# SD.net
KiCad netlist of a schematic drawn in Altium Designer
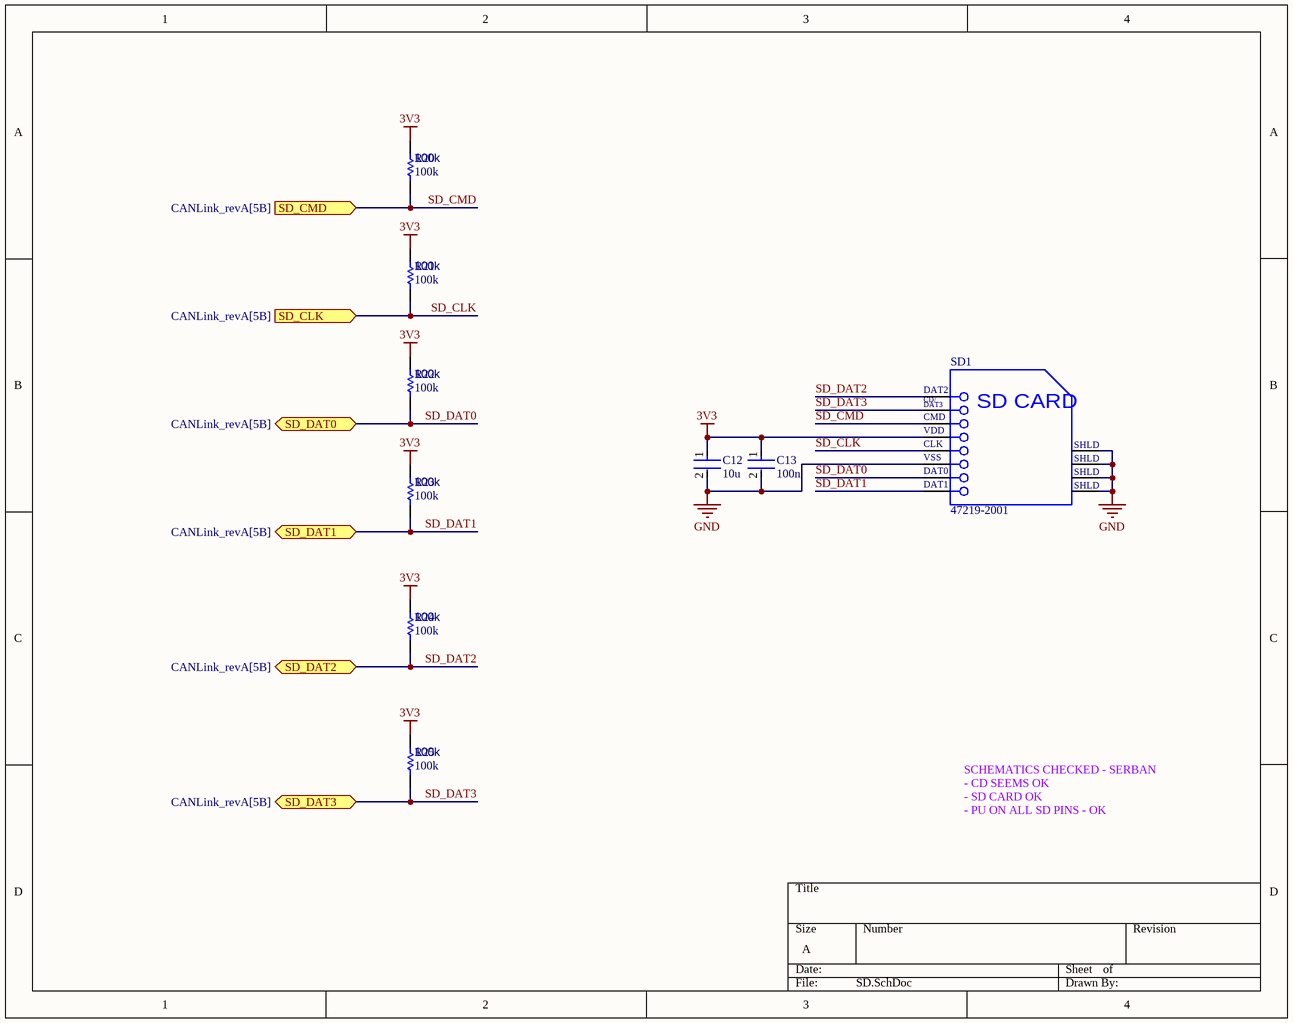
[diagram p0: SD.SchDoc]

(export (version "E")
  (design (tool "Eeschema 10.0.6"))
  (components
    (comp (ref "C12")
      (value "10u")
      (footprint "FP-0402-L_1_0_0_05-W_0_5-IPC_A")
      (description "LARGE PADS, 0402 CAP, CHANGE COMMENT TO MATCH REAL P/N")
      (libsource (lib "Space Concordia") (part "b4654b650e69147ec39a6b967a45e02"))
    )
    (comp (ref "C13")
      (value "100n")
      (footprint "FP-0402-L_1_0_0_05-W_0_5-IPC_A")
      (description "LARGE PADS, 0402 CAP, CHANGE COMMENT TO MATCH REAL P/N")
      (libsource (lib "Space Concordia") (part "b4654b650e69147ec39a6b967a45e02"))
    )
    (comp (ref "R20")
      (value "100k")
      (footprint "R0603B")
      (description "Resistor")
      (fields (field (name "ALTIUM_VALUE") "100k"))
      (libsource (lib "Space Concordia") (part "Resistor"))
    )
    (comp (ref "R21")
      (value "100k")
      (footprint "R0603B")
      (description "Resistor")
      (fields (field (name "ALTIUM_VALUE") "100k"))
      (libsource (lib "Space Concordia") (part "Resistor"))
    )
    (comp (ref "R22")
      (value "100k")
      (footprint "R0603B")
      (description "Resistor")
      (fields (field (name "ALTIUM_VALUE") "100k"))
      (libsource (lib "Space Concordia") (part "Resistor"))
    )
    (comp (ref "R23")
      (value "100k")
      (footprint "R0603B")
      (description "Resistor")
      (fields (field (name "ALTIUM_VALUE") "100k"))
      (libsource (lib "Space Concordia") (part "Resistor"))
    )
    (comp (ref "R24")
      (value "100k")
      (footprint "R0603B")
      (description "Resistor")
      (fields (field (name "ALTIUM_VALUE") "100k"))
      (libsource (lib "Space Concordia") (part "Resistor"))
    )
    (comp (ref "R25")
      (value "100k")
      (footprint "R0603B")
      (description "Resistor")
      (fields (field (name "ALTIUM_VALUE") "100k"))
      (libsource (lib "Space Concordia") (part "Resistor"))
    )
    (comp (ref "SD1")
      (value "47219-2001")
      (footprint "MOLX-47219-2001-8_V")
      (description "MicroSD Card Connector, Hinge Type, -40 to 85 degC, 8-Pin SMD, RoHS, Tape and Reel")
      (fields (field (name "MANUFACTURER") "Molex"))
      (libsource (lib "Altium Content Vault") (part "CN-SD-8-4S"))
    )
  )
  (nets
    (net (code "1") (name "/SD_CLK") (class "Default")
      (node (ref "R21") (pin "2") (pinfunction "2_2") (pintype "passive"))
      (node (ref "SD1") (pin "5") (pinfunction "CLK_5") (pintype "passive"))
    )
    (net (code "2") (name "/SD_CMD") (class "Default")
      (node (ref "R20") (pin "2") (pinfunction "2_2") (pintype "passive"))
      (node (ref "SD1") (pin "3") (pinfunction "CMD_3") (pintype "passive"))
    )
    (net (code "3") (name "/SD_DAT0") (class "Default")
      (node (ref "R22") (pin "2") (pinfunction "2_2") (pintype "passive"))
      (node (ref "SD1") (pin "7") (pinfunction "DAT0_7") (pintype "passive"))
    )
    (net (code "4") (name "/SD_DAT1") (class "Default")
      (node (ref "R23") (pin "2") (pinfunction "2_2") (pintype "passive"))
      (node (ref "SD1") (pin "8") (pinfunction "DAT1_8") (pintype "passive"))
    )
    (net (code "5") (name "/SD_DAT2") (class "Default")
      (node (ref "R24") (pin "2") (pinfunction "2_2") (pintype "passive"))
      (node (ref "SD1") (pin "1") (pinfunction "DAT2_1") (pintype "passive"))
    )
    (net (code "6") (name "/SD_DAT3") (class "Default")
      (node (ref "R25") (pin "2") (pinfunction "2_2") (pintype "passive"))
      (node (ref "SD1") (pin "2") (pinfunction "CD/DAT3_2") (pintype "passive"))
    )
    (net (code "7") (name "3V3") (class "Default")
      (node (ref "C12") (pin "1") (pinfunction "1_1") (pintype "passive"))
      (node (ref "C13") (pin "1") (pinfunction "1_1") (pintype "passive"))
      (node (ref "R20") (pin "1") (pinfunction "1_1") (pintype "passive"))
      (node (ref "R21") (pin "1") (pinfunction "1_1") (pintype "passive"))
      (node (ref "R22") (pin "1") (pinfunction "1_1") (pintype "passive"))
      (node (ref "R23") (pin "1") (pinfunction "1_1") (pintype "passive"))
      (node (ref "R24") (pin "1") (pinfunction "1_1") (pintype "passive"))
      (node (ref "R25") (pin "1") (pinfunction "1_1") (pintype "passive"))
      (node (ref "SD1") (pin "4") (pinfunction "VDD_4") (pintype "passive"))
    )
    (net (code "8") (name "GND") (class "Default")
      (node (ref "C12") (pin "2") (pinfunction "2_2") (pintype "passive"))
      (node (ref "C13") (pin "2") (pinfunction "2_2") (pintype "passive"))
      (node (ref "SD1") (pin "10") (pinfunction "SHLD_10") (pintype "passive"))
      (node (ref "SD1") (pin "11") (pinfunction "SHLD_11") (pintype "passive"))
      (node (ref "SD1") (pin "12") (pinfunction "SHLD_12") (pintype "passive"))
      (node (ref "SD1") (pin "6") (pinfunction "VSS_6") (pintype "passive"))
      (node (ref "SD1") (pin "9") (pinfunction "SHLD_9") (pintype "passive"))
    )
  )
)
